# BH_Pzem_WI_FI_SHIELD_rev_1_1.net
KiCad netlist of a schematic drawn in EAGLE
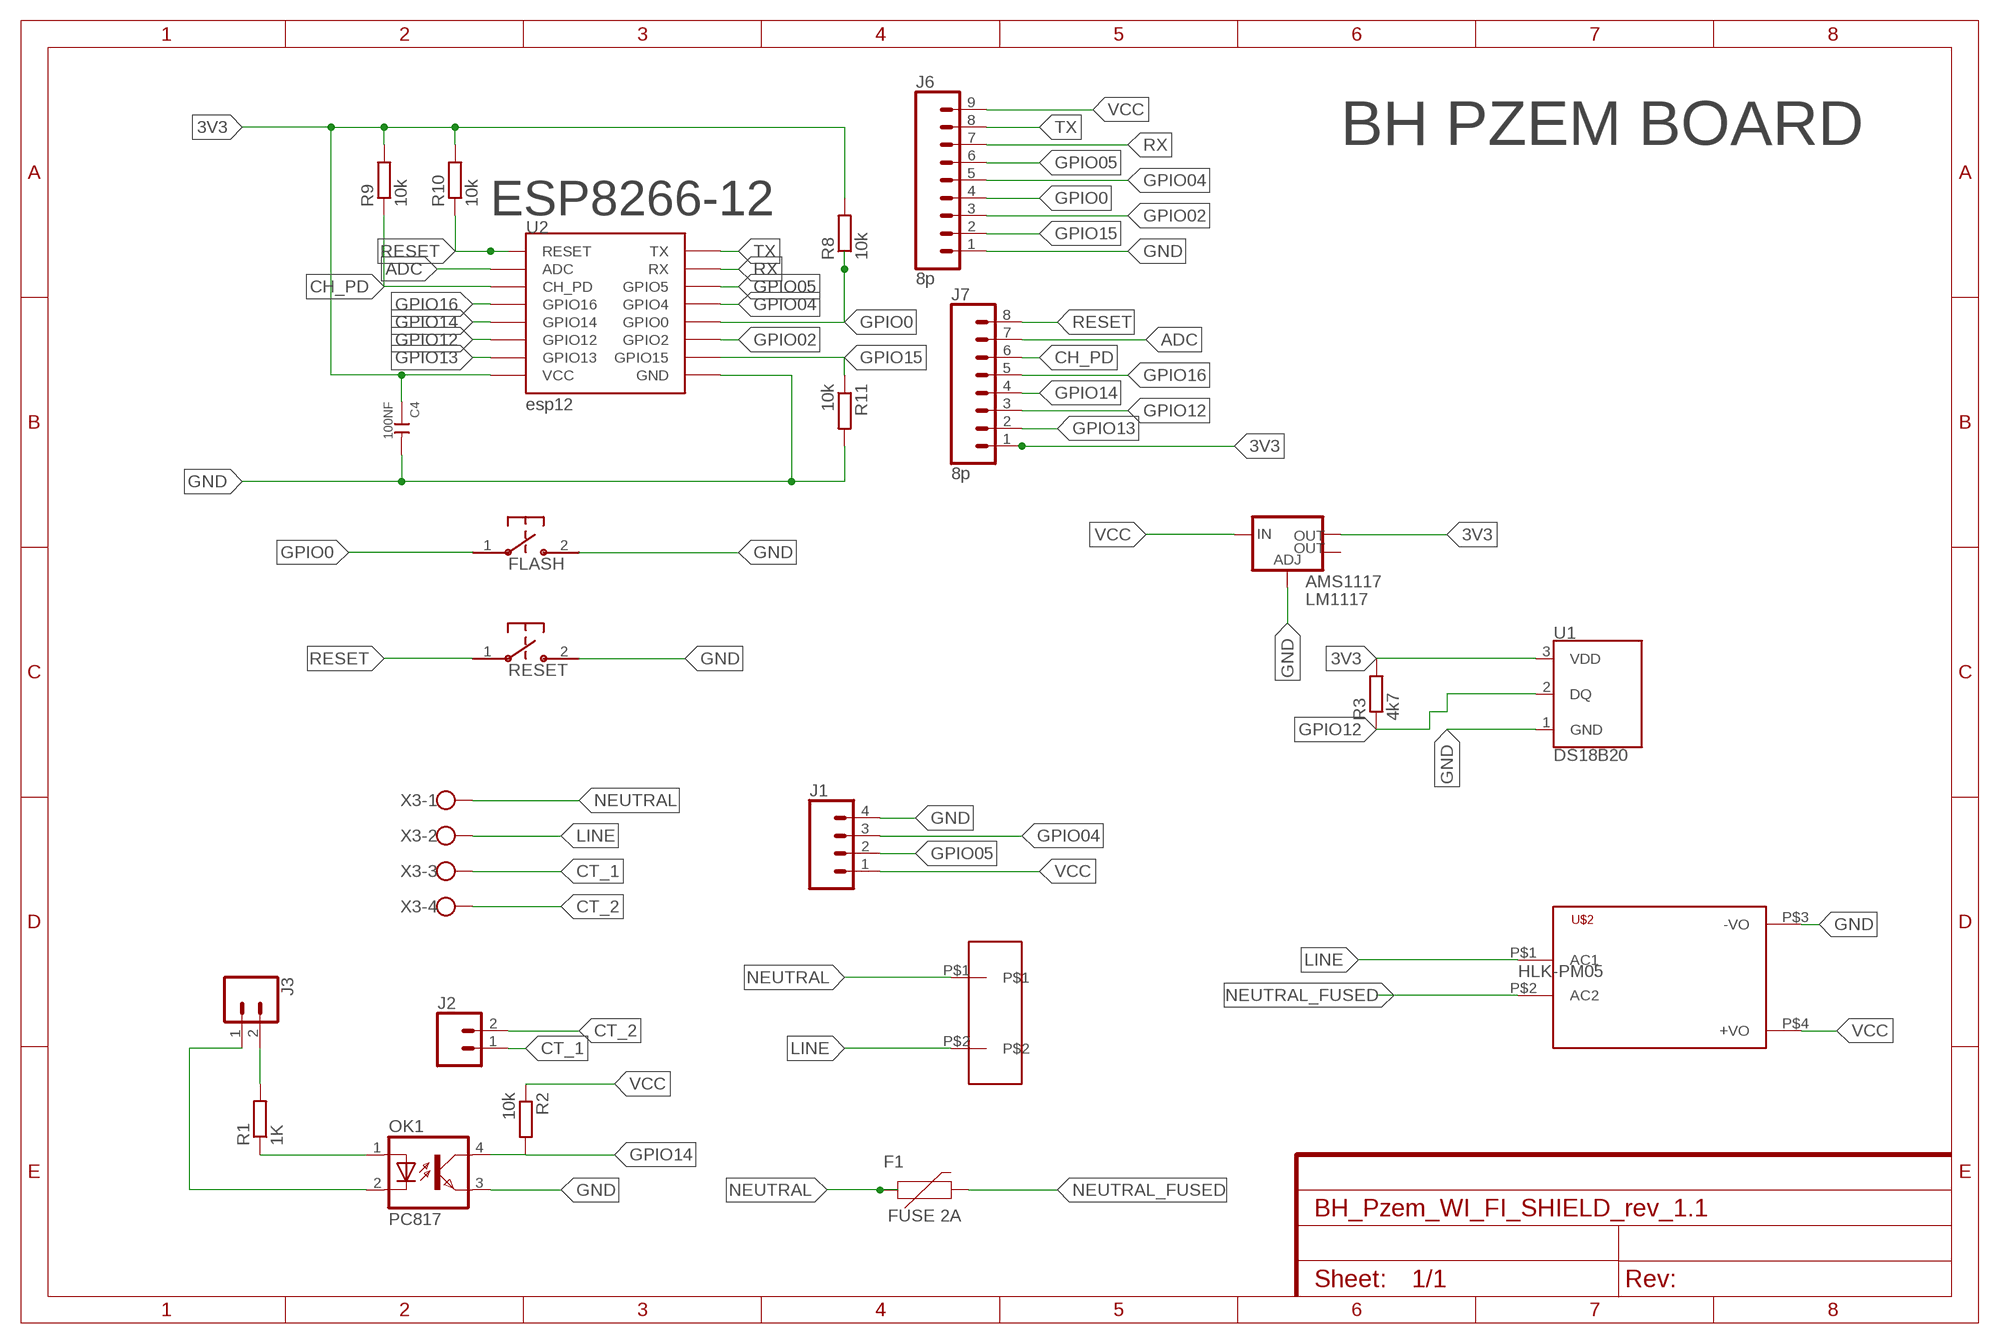
[diagram p0: schematic, sheet 1]

(export (version "E")
  (design (tool "Eeschema 10.0.6"))
  (components
    (comp (ref "AMS1117")
      (value "LM1117")
      (footprint "eagle-import:SOT223")
      (libsource (lib "eagle-import") (part "V_REG_LM1117SOT223"))
    )
    (comp (ref "C4")
      (value "100NF")
      (footprint "eagle-import:C1206")
      (fields (field (name "MPN") "CC1206KKX7RCBB102"))
      (libsource (lib "eagle-import") (part "CERAMIC-1NF-1KV-10%-X7R?(1206)"))
    )
    (comp (ref "F1")
      (value "FUSE 2A")
      (footprint "eagle-import:PTH")
      (libsource (lib "eagle-import") (part "PPTC_PTH"))
    )
    (comp (ref "FLASH")
      (value "B3U-1000P-2P-SMD")
      (footprint "eagle-import:B3U-1000P")
      (fields
        (field (name "MANUFACTURER") "Omron")
        (field (name "MPN") "B3U-1000P")
        (field (name "SPICEPREFIX") "F")
      )
      (libsource (lib "eagle-import") (part "B3U-1000P"))
    )
    (comp (ref "J1")
      (value "CONN_04")
      (footprint "eagle-import:1X04")
      (libsource (lib "eagle-import") (part "CONN_04"))
    )
    (comp (ref "J2")
      (value "CONN_02")
      (footprint "eagle-import:1X02")
      (libsource (lib "eagle-import") (part "CONN_02"))
    )
    (comp (ref "J3")
      (value "CONN_02")
      (footprint "eagle-import:1X02")
      (libsource (lib "eagle-import") (part "CONN_02"))
    )
    (comp (ref "J6")
      (value "8p")
      (footprint "eagle-import:1X09")
      (libsource (lib "eagle-import") (part "CONN_09"))
    )
    (comp (ref "J7")
      (value "8p")
      (footprint "eagle-import:1X08")
      (libsource (lib "eagle-import") (part "CONN_08{dblquote}"))
    )
    (comp (ref "OK1")
      (value "PC817")
      (footprint "eagle-import:DIL04")
      (fields (field (name "MPN") "PC817X4J000F"))
      (libsource (lib "eagle-import") (part "PC817"))
    )
    (comp (ref "R1")
      (value "1K")
      (footprint "eagle-import:R0603")
      (libsource (lib "eagle-import") (part "R-EU_R0603"))
    )
    (comp (ref "R2")
      (value "10k")
      (footprint "eagle-import:R0603")
      (libsource (lib "eagle-import") (part "R-EU_R0603"))
    )
    (comp (ref "R3")
      (value "4k7")
      (footprint "eagle-import:R0603")
      (libsource (lib "eagle-import") (part "R-EU_R0603"))
    )
    (comp (ref "R8")
      (value "10k")
      (footprint "eagle-import:R0603")
      (libsource (lib "eagle-import") (part "R-EU_R0603"))
    )
    (comp (ref "R9")
      (value "10k")
      (footprint "eagle-import:R0603")
      (libsource (lib "eagle-import") (part "R-EU_R0603"))
    )
    (comp (ref "R10")
      (value "10k")
      (footprint "eagle-import:R0603")
      (libsource (lib "eagle-import") (part "R-EU_R0603"))
    )
    (comp (ref "R11")
      (value "10k")
      (footprint "eagle-import:R0603")
      (libsource (lib "eagle-import") (part "R-EU_R0603"))
    )
    (comp (ref "RESET")
      (value "B3U-1000P-2P-SMD")
      (footprint "eagle-import:B3U-1000P")
      (fields (field (name "MANUFACTURER") "Omron") (field (name "MPN") "B3U-1000P"))
      (libsource (lib "eagle-import") (part "B3U-1000P"))
    )
    (comp (ref "U$1")
      (value "SCREWTERMINALS_5MM_2")
      (footprint "eagle-import:TERMINAL_2X")
      (libsource (lib "eagle-import") (part "SCREWTERMINALS_5MM_2"))
    )
    (comp (ref "U$2")
      (value "HKLPM01")
      (footprint "eagle-import:HKLPM01")
      (libsource (lib "eagle-import") (part "HKLPM01"))
    )
    (comp (ref "U1")
      (value "DS18B20")
      (footprint "eagle-import:TO-92-AMMO")
      (libsource (lib "eagle-import") (part "DS18B20"))
    )
    (comp (ref "U2")
      (value "esp12")
      (footprint "eagle-import:ESP12-SMD")
      (libsource (lib "eagle-import") (part "ESP12SMD"))
    )
    (comp (ref "X3")
      (value "W237-4")
      (footprint "eagle-import:W237-4")
      (libsource (lib "eagle-import") (part "W237-4"))
    )
  )
  (nets
    (net (code "1") (name "3V3") (class "Default")
      (node (ref "AMS1117") (pin "2") (pinfunction "OUT_2") (pintype "output"))
      (node (ref "C4") (pin "1") (pinfunction "1_1") (pintype "passive"))
      (node (ref "J7") (pin "1") (pinfunction "1_1") (pintype "passive"))
      (node (ref "R10") (pin "2") (pinfunction "2_2") (pintype "passive"))
      (node (ref "R3") (pin "2") (pinfunction "2_2") (pintype "passive"))
      (node (ref "R8") (pin "2") (pinfunction "2_2") (pintype "passive"))
      (node (ref "R9") (pin "2") (pinfunction "2_2") (pintype "passive"))
      (node (ref "U1") (pin "3") (pinfunction "VDD_3") (pintype "power_in"))
      (node (ref "U2") (pin "VCC") (pinfunction "VCC_VCC") (pintype "bidirectional"))
    )
    (net (code "2") (name "ADC") (class "Default")
      (node (ref "J7") (pin "7") (pinfunction "7_7") (pintype "passive"))
      (node (ref "U2") (pin "ADC") (pinfunction "ADC_ADC") (pintype "bidirectional"))
    )
    (net (code "3") (name "CH_PD") (class "Default")
      (node (ref "J7") (pin "6") (pinfunction "6_6") (pintype "passive"))
      (node (ref "R9") (pin "1") (pinfunction "1_1") (pintype "passive"))
      (node (ref "U2") (pin "CH_PD") (pinfunction "CH_PD_CH_PD") (pintype "bidirectional"))
    )
    (net (code "4") (name "CT_1") (class "Default")
      (node (ref "J2") (pin "1") (pinfunction "1_1") (pintype "passive"))
      (node (ref "X3") (pin "3") (pinfunction "KL_3") (pintype "passive"))
    )
    (net (code "5") (name "CT_2") (class "Default")
      (node (ref "J2") (pin "2") (pinfunction "2_2") (pintype "passive"))
      (node (ref "X3") (pin "4") (pinfunction "KL_4") (pintype "passive"))
    )
    (net (code "6") (name "GND") (class "Default")
      (node (ref "AMS1117") (pin "1") (pinfunction "ADJ_1") (pintype "input"))
      (node (ref "C4") (pin "2") (pinfunction "2_2") (pintype "passive"))
      (node (ref "FLASH") (pin "2") (pinfunction "P$2_2") (pintype "passive"))
      (node (ref "J1") (pin "4") (pinfunction "4_4") (pintype "passive"))
      (node (ref "J6") (pin "1") (pinfunction "1_1") (pintype "passive"))
      (node (ref "OK1") (pin "3") (pinfunction "EMIT_3") (pintype "passive"))
      (node (ref "R11") (pin "2") (pinfunction "2_2") (pintype "passive"))
      (node (ref "RESET") (pin "2") (pinfunction "P$2_2") (pintype "passive"))
      (node (ref "U$2") (pin "P$3") (pinfunction "-VO_P$3") (pintype "bidirectional"))
      (node (ref "U1") (pin "1") (pinfunction "GND_1") (pintype "power_in"))
      (node (ref "U2") (pin "GND") (pinfunction "GND_GND") (pintype "bidirectional"))
    )
    (net (code "7") (name "GPIO0") (class "Default")
      (node (ref "FLASH") (pin "1") (pinfunction "P$1_1") (pintype "passive"))
      (node (ref "J6") (pin "4") (pinfunction "4_4") (pintype "passive"))
      (node (ref "R8") (pin "1") (pinfunction "1_1") (pintype "passive"))
      (node (ref "U2") (pin "GPIO0") (pinfunction "GPIO0_GPIO0") (pintype "bidirectional"))
    )
    (net (code "8") (name "GPIO02") (class "Default")
      (node (ref "J6") (pin "3") (pinfunction "3_3") (pintype "passive"))
      (node (ref "U2") (pin "GPIO2") (pinfunction "GPIO2_GPIO2") (pintype "bidirectional"))
    )
    (net (code "9") (name "GPIO04") (class "Default")
      (node (ref "J1") (pin "3") (pinfunction "3_3") (pintype "passive"))
      (node (ref "J6") (pin "5") (pinfunction "5_5") (pintype "passive"))
      (node (ref "U2") (pin "GPIO4") (pinfunction "GPIO4_GPIO4") (pintype "bidirectional"))
    )
    (net (code "10") (name "GPIO05") (class "Default")
      (node (ref "J1") (pin "2") (pinfunction "2_2") (pintype "passive"))
      (node (ref "J6") (pin "6") (pinfunction "6_6") (pintype "passive"))
      (node (ref "U2") (pin "GPIO5") (pinfunction "GPIO5_GPIO5") (pintype "bidirectional"))
    )
    (net (code "11") (name "GPIO12") (class "Default")
      (node (ref "J7") (pin "3") (pinfunction "3_3") (pintype "passive"))
      (node (ref "R3") (pin "1") (pinfunction "1_1") (pintype "passive"))
      (node (ref "U1") (pin "2") (pinfunction "DQ_2") (pintype "bidirectional"))
      (node (ref "U2") (pin "GPIO12") (pinfunction "GPIO12_GPIO12") (pintype "bidirectional"))
    )
    (net (code "12") (name "GPIO13") (class "Default")
      (node (ref "J7") (pin "2") (pinfunction "2_2") (pintype "passive"))
      (node (ref "U2") (pin "GPIO13") (pinfunction "GPIO13_GPIO13") (pintype "bidirectional"))
    )
    (net (code "13") (name "GPIO14") (class "Default")
      (node (ref "J7") (pin "4") (pinfunction "4_4") (pintype "passive"))
      (node (ref "OK1") (pin "4") (pinfunction "COL_4") (pintype "passive"))
      (node (ref "R2") (pin "2") (pinfunction "2_2") (pintype "passive"))
      (node (ref "U2") (pin "GPIO14") (pinfunction "GPIO14_GPIO14") (pintype "bidirectional"))
    )
    (net (code "14") (name "GPIO15") (class "Default")
      (node (ref "J6") (pin "2") (pinfunction "2_2") (pintype "passive"))
      (node (ref "R11") (pin "1") (pinfunction "1_1") (pintype "passive"))
      (node (ref "U2") (pin "GPIO15") (pinfunction "GPIO15_GPIO15") (pintype "bidirectional"))
    )
    (net (code "15") (name "GPIO16") (class "Default")
      (node (ref "J7") (pin "5") (pinfunction "5_5") (pintype "passive"))
      (node (ref "U2") (pin "GPIO16") (pinfunction "GPIO16_GPIO16") (pintype "bidirectional"))
    )
    (net (code "16") (name "LINE") (class "Default")
      (node (ref "U$1") (pin "P$2") (pinfunction "P$2_P$2") (pintype "bidirectional"))
      (node (ref "U$2") (pin "P$1") (pinfunction "AC1_P$1") (pintype "bidirectional"))
      (node (ref "X3") (pin "2") (pinfunction "KL_2") (pintype "passive"))
    )
    (net (code "17") (name "NEUTRAL") (class "Default")
      (node (ref "F1") (pin "P$1") (pinfunction "1_P$1") (pintype "bidirectional"))
      (node (ref "U$1") (pin "P$1") (pinfunction "P$1_P$1") (pintype "bidirectional"))
      (node (ref "X3") (pin "1") (pinfunction "KL_1") (pintype "passive"))
    )
    (net (code "18") (name "NEUTRAL_FUSED") (class "Default")
      (node (ref "F1") (pin "P$2") (pinfunction "2_P$2") (pintype "bidirectional"))
      (node (ref "U$2") (pin "P$2") (pinfunction "AC2_P$2") (pintype "bidirectional"))
    )
    (net (code "19") (name "Net-(J3-Pad2)") (class "Default")
      (node (ref "J3") (pin "2") (pinfunction "2_2") (pintype "passive"))
      (node (ref "R1") (pin "2") (pinfunction "2_2") (pintype "passive"))
    )
    (net (code "20") (name "Net-(OK1-A)") (class "Default")
      (node (ref "OK1") (pin "1") (pinfunction "A_1") (pintype "passive"))
      (node (ref "R1") (pin "1") (pinfunction "1_1") (pintype "passive"))
    )
    (net (code "21") (name "Net-(OK1-C)") (class "Default")
      (node (ref "J3") (pin "1") (pinfunction "1_1") (pintype "passive"))
      (node (ref "OK1") (pin "2") (pinfunction "C_2") (pintype "passive"))
    )
    (net (code "22") (name "RESET") (class "Default")
      (node (ref "J7") (pin "8") (pinfunction "8_8") (pintype "passive"))
      (node (ref "R10") (pin "1") (pinfunction "1_1") (pintype "passive"))
      (node (ref "RESET") (pin "1") (pinfunction "P$1_1") (pintype "passive"))
      (node (ref "U2") (pin "RESET") (pinfunction "RESET_RESET") (pintype "bidirectional"))
    )
    (net (code "23") (name "RX") (class "Default")
      (node (ref "J6") (pin "7") (pinfunction "7_7") (pintype "passive"))
      (node (ref "U2") (pin "RXD0") (pinfunction "RX_RXD0") (pintype "bidirectional"))
    )
    (net (code "24") (name "TX") (class "Default")
      (node (ref "J6") (pin "8") (pinfunction "8_8") (pintype "passive"))
      (node (ref "U2") (pin "TXD0") (pinfunction "TX_TXD0") (pintype "bidirectional"))
    )
    (net (code "25") (name "VCC") (class "Default")
      (node (ref "AMS1117") (pin "3") (pinfunction "IN_3") (pintype "input"))
      (node (ref "J1") (pin "1") (pinfunction "1_1") (pintype "passive"))
      (node (ref "J6") (pin "9") (pinfunction "9_9") (pintype "passive"))
      (node (ref "R2") (pin "1") (pinfunction "1_1") (pintype "passive"))
      (node (ref "U$2") (pin "P$4") (pinfunction "+VO_P$4") (pintype "bidirectional"))
    )
    (net (code "26") (name "unconnected-(AMS1117-OUT-Pad4)") (class "Default")
      (node (ref "AMS1117") (pin "4") (pinfunction "OUT_4") (pintype "output"))
    )
  )
)
